# inventer.net
KiCad netlist of a schematic drawn in Altium Designer
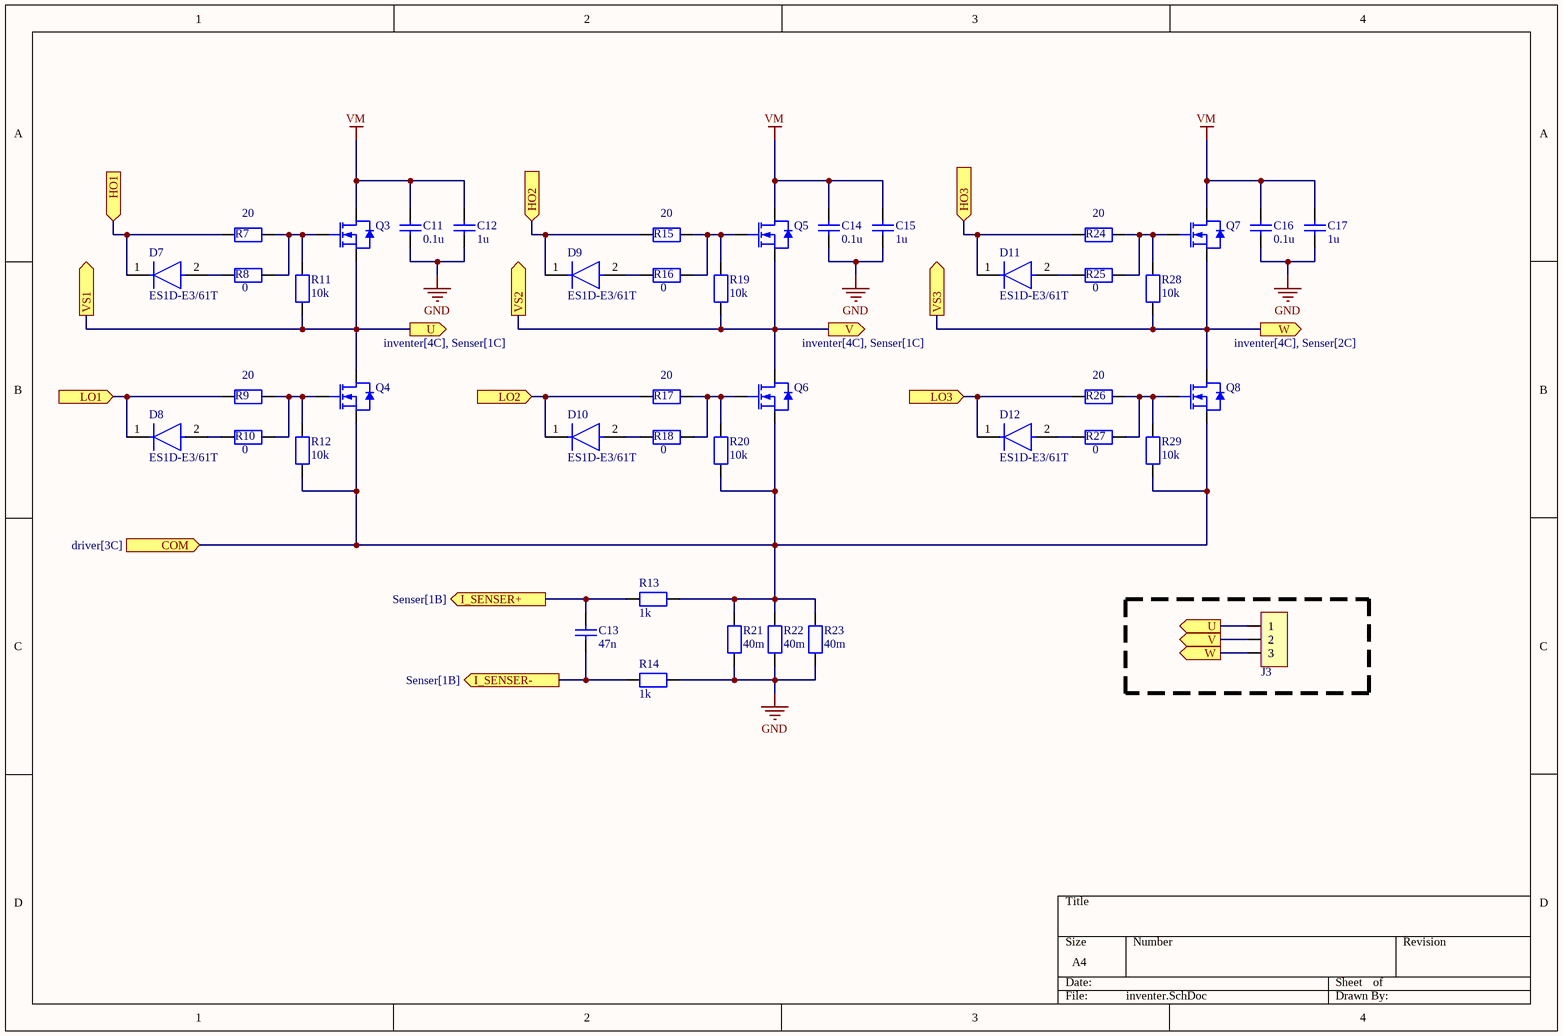
[diagram p0: inventer.SchDoc]

(export (version "E")
  (design (tool "Eeschema 10.0.6"))
  (components
    (comp (ref "C11")
      (value "0.1u")
      (footprint "CAP_1206")
      (description "Конденсатор керамический smd 0.1 мкФ X7R 50В 10% 1206,")
      (fields (field (name "Comment") "CAP"))
      (libsource (lib "Capacitors") (part "CAP"))
    )
    (comp (ref "C12")
      (value "1u")
      (footprint "CAP_1206")
      (description "Конденсатор керамический smd 1 мкФ X7R 50В,10%, 1206")
      (fields (field (name "Comment") "CAP"))
      (libsource (lib "Capacitors") (part "CAP"))
    )
    (comp (ref "C13")
      (value "47n")
      (footprint "CAPC2012X06N")
      (description "Конденсатор керамический smd 0.047мкФ X7R 50В 10% 0805")
      (fields (field (name "Comment") "CAP"))
      (libsource (lib "Capacitors") (part "CAP"))
    )
    (comp (ref "C14")
      (value "0.1u")
      (footprint "CAP_1206")
      (description "Конденсатор керамический smd 0.1 мкФ X7R 50В 10% 1206,")
      (fields (field (name "Comment") "CAP"))
      (libsource (lib "Capacitors") (part "CAP"))
    )
    (comp (ref "C15")
      (value "1u")
      (footprint "CAP_1206")
      (description "Конденсатор керамический smd 1 мкФ X7R 50В,10%, 1206")
      (fields (field (name "Comment") "CAP"))
      (libsource (lib "Capacitors") (part "CAP"))
    )
    (comp (ref "C16")
      (value "0.1u")
      (footprint "CAP_1206")
      (description "Конденсатор керамический smd 0.1 мкФ X7R 50В 10% 1206,")
      (fields (field (name "Comment") "CAP"))
      (libsource (lib "Capacitors") (part "CAP"))
    )
    (comp (ref "C17")
      (value "1u")
      (footprint "CAP_1206")
      (description "Конденсатор керамический smd 1 мкФ X7R 50В,10%, 1206")
      (fields (field (name "Comment") "CAP"))
      (libsource (lib "Capacitors") (part "CAP"))
    )
    (comp (ref "D7")
      (value "ES1D-E3/61T")
      (footprint "FP-95400-MFG")
      (description "DIODE GEN PURP 200V 1A DO214AC")
      (fields
        (field (name "MANUFACTURER") "Vishay")
        (field (name "OCTOPART") "https://octopart.com/es1d-e3%2F61t-vishay-39550266")
      )
      (libsource (lib "Altium Content Vault") (part "d7152d700b627762746794eb795d46e"))
    )
    (comp (ref "D8")
      (value "ES1D-E3/61T")
      (footprint "FP-95400-MFG")
      (description "DIODE GEN PURP 200V 1A DO214AC")
      (fields
        (field (name "MANUFACTURER") "Vishay")
        (field (name "OCTOPART") "https://octopart.com/es1d-e3%2F61t-vishay-39550266")
      )
      (libsource (lib "Altium Content Vault") (part "d7152d700b627762746794eb795d46e"))
    )
    (comp (ref "D9")
      (value "ES1D-E3/61T")
      (footprint "FP-95400-MFG")
      (description "DIODE GEN PURP 200V 1A DO214AC")
      (fields
        (field (name "MANUFACTURER") "Vishay")
        (field (name "OCTOPART") "https://octopart.com/es1d-e3%2F61t-vishay-39550266")
      )
      (libsource (lib "Altium Content Vault") (part "d7152d700b627762746794eb795d46e"))
    )
    (comp (ref "D10")
      (value "ES1D-E3/61T")
      (footprint "FP-95400-MFG")
      (description "DIODE GEN PURP 200V 1A DO214AC")
      (fields
        (field (name "MANUFACTURER") "Vishay")
        (field (name "OCTOPART") "https://octopart.com/es1d-e3%2F61t-vishay-39550266")
      )
      (libsource (lib "Altium Content Vault") (part "d7152d700b627762746794eb795d46e"))
    )
    (comp (ref "D11")
      (value "ES1D-E3/61T")
      (footprint "FP-95400-MFG")
      (description "DIODE GEN PURP 200V 1A DO214AC")
      (fields
        (field (name "MANUFACTURER") "Vishay")
        (field (name "OCTOPART") "https://octopart.com/es1d-e3%2F61t-vishay-39550266")
      )
      (libsource (lib "Altium Content Vault") (part "d7152d700b627762746794eb795d46e"))
    )
    (comp (ref "D12")
      (value "ES1D-E3/61T")
      (footprint "FP-95400-MFG")
      (description "DIODE GEN PURP 200V 1A DO214AC")
      (fields
        (field (name "MANUFACTURER") "Vishay")
        (field (name "OCTOPART") "https://octopart.com/es1d-e3%2F61t-vishay-39550266")
      )
      (libsource (lib "Altium Content Vault") (part "d7152d700b627762746794eb795d46e"))
    )
    (comp (ref "J3") (value "Power 3") (footprint "Power 3") (libsource (lib "bldc_lib") (part "Power 3")))
    (comp (ref "Q3")
      (value "IRF1010ZSTRLPBF")
      (footprint "FP-PG-TO263-3-MFG")
      (description "IRF1010ZSTRLPBF, Транзистор HEXFET N-канал 55В 75А")
      (fields (field (name "SOURCE") "https://www.chipdip.ru/product/irf1010zstrlpbf-infineon"))
      (libsource (lib "Transistors") (part "NMOS"))
    )
    (comp (ref "Q4")
      (value "IRF1010ZSTRLPBF")
      (footprint "FP-PG-TO263-3-MFG")
      (description "IRF1010ZSTRLPBF, Транзистор HEXFET N-канал 55В 75А")
      (fields (field (name "SOURCE") "https://www.chipdip.ru/product/irf1010zstrlpbf-infineon"))
      (libsource (lib "Transistors") (part "NMOS"))
    )
    (comp (ref "Q5")
      (value "IRF1010ZSTRLPBF")
      (footprint "FP-PG-TO263-3-MFG")
      (description "IRF1010ZSTRLPBF, Транзистор HEXFET N-канал 55В 75А")
      (fields (field (name "SOURCE") "https://www.chipdip.ru/product/irf1010zstrlpbf-infineon"))
      (libsource (lib "Transistors") (part "NMOS"))
    )
    (comp (ref "Q6")
      (value "IRF1010ZSTRLPBF")
      (footprint "FP-PG-TO263-3-MFG")
      (description "IRF1010ZSTRLPBF, Транзистор HEXFET N-канал 55В 75А")
      (fields (field (name "SOURCE") "https://www.chipdip.ru/product/irf1010zstrlpbf-infineon"))
      (libsource (lib "Transistors") (part "NMOS"))
    )
    (comp (ref "Q7")
      (value "IRF1010ZSTRLPBF")
      (footprint "FP-PG-TO263-3-MFG")
      (description "IRF1010ZSTRLPBF, Транзистор HEXFET N-канал 55В 75А")
      (fields (field (name "SOURCE") "https://www.chipdip.ru/product/irf1010zstrlpbf-infineon"))
      (libsource (lib "Transistors") (part "NMOS"))
    )
    (comp (ref "Q8")
      (value "IRF1010ZSTRLPBF")
      (footprint "FP-PG-TO263-3-MFG")
      (description "IRF1010ZSTRLPBF, Транзистор HEXFET N-канал 55В 75А")
      (fields (field (name "SOURCE") "https://www.chipdip.ru/product/irf1010zstrlpbf-infineon"))
      (libsource (lib "Transistors") (part "NMOS"))
    )
    (comp (ref "R7")
      (value "20")
      (footprint "RESC3016X06N")
      (description "0.25Вт 1206 20 Ом, 1%")
      (fields (field (name "Comment") "1k"))
      (libsource (lib "Resistor") (part "Resistor"))
    )
    (comp (ref "R8")
      (value "0")
      (footprint "RESC3016X06N")
      (description "0.25Вт 1206 (перемычка) 0 Ом")
      (fields (field (name "Comment") "1k"))
      (libsource (lib "Resistor") (part "Resistor"))
    )
    (comp (ref "R9")
      (value "20")
      (footprint "RESC3016X06N")
      (description "0.25Вт 1206 20 Ом, 1%")
      (fields (field (name "Comment") "1k"))
      (libsource (lib "Resistor") (part "Resistor"))
    )
    (comp (ref "R10")
      (value "0")
      (footprint "RESC3016X06N")
      (description "0.25Вт 1206 (перемычка) 0 Ом")
      (fields (field (name "Comment") "1k"))
      (libsource (lib "Resistor") (part "Resistor"))
    )
    (comp (ref "R11")
      (value "10k")
      (footprint "RESC2012X06N")
      (description "0.125Вт 0805 10 кОм, 1%")
      (libsource (lib "Resistor") (part "Resistor"))
    )
    (comp (ref "R12")
      (value "10k")
      (footprint "RESC2012X06N")
      (description "0.125Вт 0805 10 кОм, 1%")
      (libsource (lib "Resistor") (part "Resistor"))
    )
    (comp (ref "R13")
      (value "1k")
      (footprint "RESC2012X06N")
      (description "0.125Вт 0805 1 кОм, 1%")
      (fields (field (name "Comment") "Resistor"))
      (libsource (lib "Resistor") (part "Resistor"))
    )
    (comp (ref "R14")
      (value "1k")
      (footprint "RESC2012X06N")
      (description "0.125Вт 0805 1 кОм, 1%")
      (fields (field (name "Comment") "Resistor"))
      (libsource (lib "Resistor") (part "Resistor"))
    )
    (comp (ref "R15")
      (value "20")
      (footprint "RESC3016X06N")
      (description "0.25Вт 1206 20 Ом, 1%")
      (fields (field (name "Comment") "1k"))
      (libsource (lib "Resistor") (part "Resistor"))
    )
    (comp (ref "R16")
      (value "0")
      (footprint "RESC3016X06N")
      (description "0.25Вт 1206 (перемычка) 0 Ом")
      (fields (field (name "Comment") "1k"))
      (libsource (lib "Resistor") (part "Resistor"))
    )
    (comp (ref "R17")
      (value "20")
      (footprint "RESC3016X06N")
      (description "0.25Вт 1206 20 Ом, 1%")
      (fields (field (name "Comment") "1k"))
      (libsource (lib "Resistor") (part "Resistor"))
    )
    (comp (ref "R18")
      (value "0")
      (footprint "RESC3016X06N")
      (description "0.25Вт 1206 (перемычка) 0 Ом")
      (fields (field (name "Comment") "1k"))
      (libsource (lib "Resistor") (part "Resistor"))
    )
    (comp (ref "R19")
      (value "10k")
      (footprint "RESC2012X06N")
      (description "0.125Вт 0805 10 кОм, 1%")
      (libsource (lib "Resistor") (part "Resistor"))
    )
    (comp (ref "R20")
      (value "10k")
      (footprint "RESC2012X06N")
      (description "0.125Вт 0805 10 кОм, 1%")
      (libsource (lib "Resistor") (part "Resistor"))
    )
    (comp (ref "R21")
      (value "40m")
      (footprint "RESC2512")
      (fields (field (name "Comment") "Resistor"))
      (libsource (lib "Resistor") (part "Resistor"))
    )
    (comp (ref "R22")
      (value "40m")
      (footprint "RESC2512")
      (fields (field (name "Comment") "Resistor"))
      (libsource (lib "Resistor") (part "Resistor"))
    )
    (comp (ref "R23")
      (value "40m")
      (footprint "RESC2512")
      (fields (field (name "Comment") "Resistor"))
      (libsource (lib "Resistor") (part "Resistor"))
    )
    (comp (ref "R24")
      (value "20")
      (footprint "RESC3016X06N")
      (description "0.25Вт 1206 20 Ом, 1%")
      (fields (field (name "Comment") "1k"))
      (libsource (lib "Resistor") (part "Resistor"))
    )
    (comp (ref "R25")
      (value "0")
      (footprint "RESC3016X06N")
      (description "0.25Вт 1206 (перемычка) 0 Ом")
      (fields (field (name "Comment") "1k"))
      (libsource (lib "Resistor") (part "Resistor"))
    )
    (comp (ref "R26")
      (value "20")
      (footprint "RESC3016X06N")
      (description "0.25Вт 1206 20 Ом, 1%")
      (fields (field (name "Comment") "1k"))
      (libsource (lib "Resistor") (part "Resistor"))
    )
    (comp (ref "R27")
      (value "0")
      (footprint "RESC3016X06N")
      (description "0.25Вт 1206 (перемычка) 0 Ом")
      (fields (field (name "Comment") "1k"))
      (libsource (lib "Resistor") (part "Resistor"))
    )
    (comp (ref "R28")
      (value "10k")
      (footprint "RESC2012X06N")
      (description "0.125Вт 0805 10 кОм, 1%")
      (libsource (lib "Resistor") (part "Resistor"))
    )
    (comp (ref "R29")
      (value "10k")
      (footprint "RESC2012X06N")
      (description "0.125Вт 0805 10 кОм, 1%")
      (libsource (lib "Resistor") (part "Resistor"))
    )
  )
  (nets
    (net (code "1") (name "/COM") (class "Default")
      (node (ref "Q4") (pin "S") (pinfunction "S_S") (pintype "passive"))
      (node (ref "Q6") (pin "S") (pinfunction "S_S") (pintype "passive"))
      (node (ref "Q8") (pin "S") (pinfunction "S_S") (pintype "passive"))
      (node (ref "R12") (pin "1") (pinfunction "*_1") (pintype "passive"))
      (node (ref "R13") (pin "1") (pinfunction "*_1") (pintype "passive"))
      (node (ref "R20") (pin "1") (pinfunction "*_1") (pintype "passive"))
      (node (ref "R21") (pin "2") (pinfunction "*_2") (pintype "passive"))
      (node (ref "R22") (pin "2") (pinfunction "*_2") (pintype "passive"))
      (node (ref "R23") (pin "2") (pinfunction "*_2") (pintype "passive"))
      (node (ref "R29") (pin "1") (pinfunction "*_1") (pintype "passive"))
    )
    (net (code "2") (name "/HO1") (class "Default")
      (node (ref "D7") (pin "1") (pinfunction "C_1") (pintype "passive"))
      (node (ref "R7") (pin "1") (pinfunction "*_1") (pintype "passive"))
    )
    (net (code "3") (name "/HO2") (class "Default")
      (node (ref "D9") (pin "1") (pinfunction "C_1") (pintype "passive"))
      (node (ref "R15") (pin "1") (pinfunction "*_1") (pintype "passive"))
    )
    (net (code "4") (name "/HO3") (class "Default")
      (node (ref "D11") (pin "1") (pinfunction "C_1") (pintype "passive"))
      (node (ref "R24") (pin "1") (pinfunction "*_1") (pintype "passive"))
    )
    (net (code "5") (name "/I_SENSER+") (class "Default")
      (node (ref "C13") (pin "1") (pinfunction "2_1") (pintype "passive"))
      (node (ref "R13") (pin "2") (pinfunction "*_2") (pintype "passive"))
    )
    (net (code "6") (name "/I_SENSER-") (class "Default")
      (node (ref "C13") (pin "2") (pinfunction "1_2") (pintype "passive"))
      (node (ref "R14") (pin "2") (pinfunction "*_2") (pintype "passive"))
    )
    (net (code "7") (name "/LO1") (class "Default")
      (node (ref "D8") (pin "1") (pinfunction "C_1") (pintype "passive"))
      (node (ref "R9") (pin "1") (pinfunction "*_1") (pintype "passive"))
    )
    (net (code "8") (name "/LO2") (class "Default")
      (node (ref "D10") (pin "1") (pinfunction "C_1") (pintype "passive"))
      (node (ref "R17") (pin "1") (pinfunction "*_1") (pintype "passive"))
    )
    (net (code "9") (name "/LO3") (class "Default")
      (node (ref "D12") (pin "1") (pinfunction "C_1") (pintype "passive"))
      (node (ref "R26") (pin "1") (pinfunction "*_1") (pintype "passive"))
    )
    (net (code "10") (name "/U") (class "Default")
      (node (ref "J3") (pin "1") (pinfunction "1_1") (pintype "passive"))
      (node (ref "Q3") (pin "S") (pinfunction "S_S") (pintype "passive"))
      (node (ref "Q4") (pin "D") (pinfunction "D_D") (pintype "passive"))
      (node (ref "R11") (pin "1") (pinfunction "*_1") (pintype "passive"))
    )
    (net (code "11") (name "/V") (class "Default")
      (node (ref "J3") (pin "2") (pinfunction "2_2") (pintype "passive"))
      (node (ref "Q5") (pin "S") (pinfunction "S_S") (pintype "passive"))
      (node (ref "Q6") (pin "D") (pinfunction "D_D") (pintype "passive"))
      (node (ref "R19") (pin "1") (pinfunction "*_1") (pintype "passive"))
    )
    (net (code "12") (name "/VS3") (class "Default")
      (node (ref "J3") (pin "3") (pinfunction "3_3") (pintype "passive"))
      (node (ref "Q7") (pin "S") (pinfunction "S_S") (pintype "passive"))
      (node (ref "Q8") (pin "D") (pinfunction "D_D") (pintype "passive"))
      (node (ref "R28") (pin "1") (pinfunction "*_1") (pintype "passive"))
    )
    (net (code "13") (name "GND") (class "Default")
      (node (ref "C11") (pin "2") (pinfunction "1_2") (pintype "passive"))
      (node (ref "C12") (pin "2") (pinfunction "1_2") (pintype "passive"))
      (node (ref "C14") (pin "2") (pinfunction "1_2") (pintype "passive"))
      (node (ref "C15") (pin "2") (pinfunction "1_2") (pintype "passive"))
      (node (ref "C16") (pin "2") (pinfunction "1_2") (pintype "passive"))
      (node (ref "C17") (pin "2") (pinfunction "1_2") (pintype "passive"))
      (node (ref "R14") (pin "1") (pinfunction "*_1") (pintype "passive"))
      (node (ref "R21") (pin "1") (pinfunction "*_1") (pintype "passive"))
      (node (ref "R22") (pin "1") (pinfunction "*_1") (pintype "passive"))
      (node (ref "R23") (pin "1") (pinfunction "*_1") (pintype "passive"))
    )
    (net (code "14") (name "Net-(D7-A)") (class "Default")
      (node (ref "D7") (pin "2") (pinfunction "A_2") (pintype "passive"))
      (node (ref "R8") (pin "1") (pinfunction "*_1") (pintype "passive"))
    )
    (net (code "15") (name "Net-(D8-A)") (class "Default")
      (node (ref "D8") (pin "2") (pinfunction "A_2") (pintype "passive"))
      (node (ref "R10") (pin "1") (pinfunction "*_1") (pintype "passive"))
    )
    (net (code "16") (name "Net-(D9-A)") (class "Default")
      (node (ref "D9") (pin "2") (pinfunction "A_2") (pintype "passive"))
      (node (ref "R16") (pin "1") (pinfunction "*_1") (pintype "passive"))
    )
    (net (code "17") (name "Net-(D10-A)") (class "Default")
      (node (ref "D10") (pin "2") (pinfunction "A_2") (pintype "passive"))
      (node (ref "R18") (pin "1") (pinfunction "*_1") (pintype "passive"))
    )
    (net (code "18") (name "Net-(D11-A)") (class "Default")
      (node (ref "D11") (pin "2") (pinfunction "A_2") (pintype "passive"))
      (node (ref "R25") (pin "1") (pinfunction "*_1") (pintype "passive"))
    )
    (net (code "19") (name "Net-(D12-A)") (class "Default")
      (node (ref "D12") (pin "2") (pinfunction "A_2") (pintype "passive"))
      (node (ref "R27") (pin "1") (pinfunction "*_1") (pintype "passive"))
    )
    (net (code "20") (name "Net-(Q3-PadG)") (class "Default")
      (node (ref "Q3") (pin "G") (pinfunction "G_G") (pintype "passive"))
      (node (ref "R11") (pin "2") (pinfunction "*_2") (pintype "passive"))
      (node (ref "R7") (pin "2") (pinfunction "*_2") (pintype "passive"))
      (node (ref "R8") (pin "2") (pinfunction "*_2") (pintype "passive"))
    )
    (net (code "21") (name "Net-(Q4-PadG)") (class "Default")
      (node (ref "Q4") (pin "G") (pinfunction "G_G") (pintype "passive"))
      (node (ref "R10") (pin "2") (pinfunction "*_2") (pintype "passive"))
      (node (ref "R12") (pin "2") (pinfunction "*_2") (pintype "passive"))
      (node (ref "R9") (pin "2") (pinfunction "*_2") (pintype "passive"))
    )
    (net (code "22") (name "Net-(Q5-PadG)") (class "Default")
      (node (ref "Q5") (pin "G") (pinfunction "G_G") (pintype "passive"))
      (node (ref "R15") (pin "2") (pinfunction "*_2") (pintype "passive"))
      (node (ref "R16") (pin "2") (pinfunction "*_2") (pintype "passive"))
      (node (ref "R19") (pin "2") (pinfunction "*_2") (pintype "passive"))
    )
    (net (code "23") (name "Net-(Q6-PadG)") (class "Default")
      (node (ref "Q6") (pin "G") (pinfunction "G_G") (pintype "passive"))
      (node (ref "R17") (pin "2") (pinfunction "*_2") (pintype "passive"))
      (node (ref "R18") (pin "2") (pinfunction "*_2") (pintype "passive"))
      (node (ref "R20") (pin "2") (pinfunction "*_2") (pintype "passive"))
    )
    (net (code "24") (name "Net-(Q7-PadG)") (class "Default")
      (node (ref "Q7") (pin "G") (pinfunction "G_G") (pintype "passive"))
      (node (ref "R24") (pin "2") (pinfunction "*_2") (pintype "passive"))
      (node (ref "R25") (pin "2") (pinfunction "*_2") (pintype "passive"))
      (node (ref "R28") (pin "2") (pinfunction "*_2") (pintype "passive"))
    )
    (net (code "25") (name "Net-(Q8-PadG)") (class "Default")
      (node (ref "Q8") (pin "G") (pinfunction "G_G") (pintype "passive"))
      (node (ref "R26") (pin "2") (pinfunction "*_2") (pintype "passive"))
      (node (ref "R27") (pin "2") (pinfunction "*_2") (pintype "passive"))
      (node (ref "R29") (pin "2") (pinfunction "*_2") (pintype "passive"))
    )
    (net (code "26") (name "VM") (class "Default")
      (node (ref "C11") (pin "1") (pinfunction "2_1") (pintype "passive"))
      (node (ref "C12") (pin "1") (pinfunction "2_1") (pintype "passive"))
      (node (ref "C14") (pin "1") (pinfunction "2_1") (pintype "passive"))
      (node (ref "C15") (pin "1") (pinfunction "2_1") (pintype "passive"))
      (node (ref "C16") (pin "1") (pinfunction "2_1") (pintype "passive"))
      (node (ref "C17") (pin "1") (pinfunction "2_1") (pintype "passive"))
      (node (ref "Q3") (pin "D") (pinfunction "D_D") (pintype "passive"))
      (node (ref "Q5") (pin "D") (pinfunction "D_D") (pintype "passive"))
      (node (ref "Q7") (pin "D") (pinfunction "D_D") (pintype "passive"))
    )
  )
)
